# 1stschem.net
KiCad netlist of a schematic drawn in EAGLE
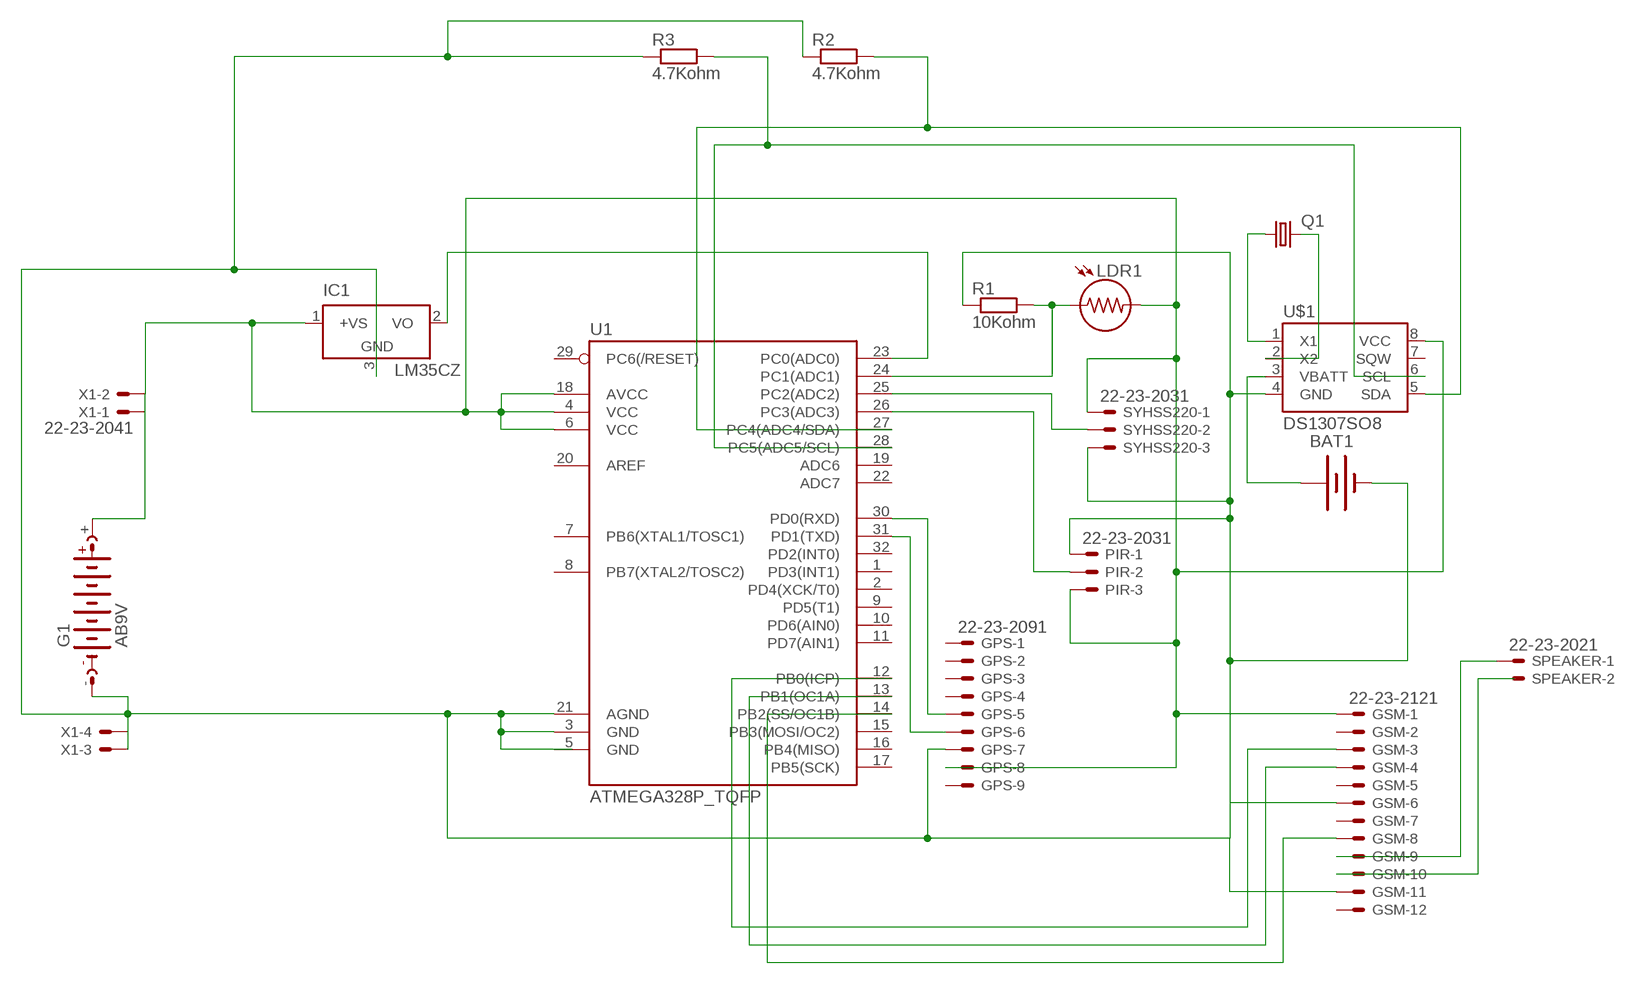
[diagram p0: schematic, sheet 1]

(export (version "E")
  (design (tool "Eeschema 10.0.6"))
  (components
    (comp (ref "BAT1")
      (value "BATTERY20PTH")
      (footprint "eagle-import:BATTCOM_20MM_PTH")
      (libsource (lib "eagle-import") (part "BATTERY20PTH"))
    )
    (comp (ref "G1")
      (value "AB9V")
      (footprint "eagle-import:AB9V")
      (libsource (lib "eagle-import") (part "AB9V"))
    )
    (comp (ref "GPS")
      (value "22-23-2091")
      (footprint "eagle-import:22-23-2091")
      (fields (field (name "MF") "MOLEX"))
      (libsource (lib "eagle-import") (part "22-23-2091"))
    )
    (comp (ref "GSM")
      (value "22-23-2121")
      (footprint "eagle-import:22-23-2121")
      (fields (field (name "MF") "MOLEX"))
      (libsource (lib "eagle-import") (part "22-23-2121"))
    )
    (comp (ref "IC1")
      (value "LM35CZ")
      (footprint "eagle-import:TO92")
      (libsource (lib "eagle-import") (part "LM35CZ"))
    )
    (comp (ref "LDR1")
      (value "LDR5MM")
      (footprint "eagle-import:LDR338-54C")
      (libsource (lib "eagle-import") (part "LDR5MM"))
    )
    (comp (ref "PIR")
      (value "22-23-2031")
      (footprint "eagle-import:22-23-2031")
      (fields (field (name "MF") "MOLEX"))
      (libsource (lib "eagle-import") (part "22-23-2031"))
    )
    (comp (ref "Q1")
      (value "CRYSTALTC26H")
      (footprint "eagle-import:TC26H")
      (libsource (lib "eagle-import") (part "CRYSTALTC26H"))
    )
    (comp (ref "R1")
      (value "10Kohm")
      (footprint "eagle-import:R0207_4")
      (libsource (lib "eagle-import") (part "6MM-EU4"))
    )
    (comp (ref "R2")
      (value "4.7Kohm")
      (footprint "eagle-import:R0207_4")
      (libsource (lib "eagle-import") (part "6MM-EU4"))
    )
    (comp (ref "R3")
      (value "4.7Kohm")
      (footprint "eagle-import:R0207_4")
      (libsource (lib "eagle-import") (part "6MM-EU4"))
    )
    (comp (ref "SPEAKER")
      (value "22-23-2021")
      (footprint "eagle-import:22-23-2021")
      (fields (field (name "MF") "MOLEX"))
      (libsource (lib "eagle-import") (part "22-23-2021"))
    )
    (comp (ref "SYHSS220")
      (value "22-23-2031")
      (footprint "eagle-import:22-23-2031")
      (fields (field (name "MF") "MOLEX"))
      (libsource (lib "eagle-import") (part "22-23-2031"))
    )
    (comp (ref "U$1")
      (value "DS1307SO8")
      (footprint "eagle-import:SO08")
      (libsource (lib "eagle-import") (part "DS1307SO8"))
    )
    (comp (ref "U1")
      (value "ATMEGA328P_TQFP")
      (footprint "eagle-import:TQFP32-08")
      (libsource (lib "eagle-import") (part "ATMEGA328P_TQFP"))
    )
    (comp (ref "X1")
      (value "22-23-2041")
      (footprint "eagle-import:22-23-2041")
      (fields (field (name "MF") "MOLEX"))
      (libsource (lib "eagle-import") (part "22-23-2041"))
    )
  )
  (nets
    (net (code "1") (name "Net-(BAT1-+)") (class "Default")
      (node (ref "BAT1") (pin "1") (pinfunction "+_1") (pintype "power_in"))
      (node (ref "U$1") (pin "3") (pinfunction "VBATT_3") (pintype "bidirectional"))
    )
    (net (code "2") (name "Net-(BAT1--)") (class "Default")
      (node (ref "BAT1") (pin "2") (pinfunction "-_2") (pintype "power_in"))
      (node (ref "G1") (pin "-") (pinfunction "-_-") (pintype "passive"))
      (node (ref "GPS") (pin "7") (pinfunction "S_7") (pintype "passive"))
      (node (ref "GSM") (pin "11") (pinfunction "S_11") (pintype "passive"))
      (node (ref "GSM") (pin "6") (pinfunction "S_6") (pintype "passive"))
      (node (ref "IC1") (pin "3") (pinfunction "GND_3") (pintype "power_in"))
      (node (ref "PIR") (pin "1") (pinfunction "S_1") (pintype "passive"))
      (node (ref "R1") (pin "1") (pinfunction "1_1") (pintype "passive"))
      (node (ref "R2") (pin "1") (pinfunction "1_1") (pintype "passive"))
      (node (ref "R3") (pin "1") (pinfunction "1_1") (pintype "passive"))
      (node (ref "SYHSS220") (pin "3") (pinfunction "S_3") (pintype "passive"))
      (node (ref "U$1") (pin "4") (pinfunction "GND_4") (pintype "bidirectional"))
      (node (ref "U1") (pin "21") (pinfunction "AGND_21") (pintype "bidirectional"))
      (node (ref "U1") (pin "3") (pinfunction "GND_3") (pintype "bidirectional"))
      (node (ref "X1") (pin "3") (pinfunction "S_3") (pintype "passive"))
      (node (ref "X1") (pin "4") (pinfunction "S_4") (pintype "passive"))
    )
    (net (code "3") (name "Net-(GPSE-S)") (class "Default")
      (node (ref "GPS") (pin "5") (pinfunction "S_5") (pintype "passive"))
      (node (ref "U1") (pin "30") (pinfunction "PD0(RXD)_30") (pintype "bidirectional"))
    )
    (net (code "4") (name "Net-(GPSF-S)") (class "Default")
      (node (ref "GPS") (pin "6") (pinfunction "S_6") (pintype "passive"))
      (node (ref "U1") (pin "31") (pinfunction "PD1(TXD)_31") (pintype "bidirectional"))
    )
    (net (code "5") (name "Net-(GPSH-S)") (class "Default")
      (node (ref "G1") (pin "+") (pinfunction "+_+") (pintype "passive"))
      (node (ref "GPS") (pin "8") (pinfunction "S_8") (pintype "passive"))
      (node (ref "GSM") (pin "1") (pinfunction "S_1") (pintype "passive"))
      (node (ref "IC1") (pin "1") (pinfunction "+VS_1") (pintype "input"))
      (node (ref "LDR1") (pin "2") (pinfunction "2_2") (pintype "passive"))
      (node (ref "PIR") (pin "3") (pinfunction "S_3") (pintype "passive"))
      (node (ref "SYHSS220") (pin "1") (pinfunction "S_1") (pintype "passive"))
      (node (ref "U$1") (pin "8") (pinfunction "VCC_8") (pintype "bidirectional"))
      (node (ref "U1") (pin "18") (pinfunction "AVCC_18") (pintype "bidirectional"))
      (node (ref "U1") (pin "4") (pinfunction "VCC_4") (pintype "bidirectional"))
      (node (ref "U1") (pin "6") (pinfunction "VCC_6") (pintype "bidirectional"))
      (node (ref "X1") (pin "1") (pinfunction "S_1") (pintype "passive"))
      (node (ref "X1") (pin "2") (pinfunction "S_2") (pintype "passive"))
    )
    (net (code "6") (name "Net-(GSMF-S)") (class "Default")
      (node (ref "GSM") (pin "3") (pinfunction "S_3") (pintype "passive"))
      (node (ref "U1") (pin "12") (pinfunction "PB0(ICP)_12") (pintype "bidirectional"))
    )
    (net (code "7") (name "Net-(GSMG-S)") (class "Default")
      (node (ref "GSM") (pin "4") (pinfunction "S_4") (pintype "passive"))
      (node (ref "U1") (pin "13") (pinfunction "PB1(OC1A)_13") (pintype "bidirectional"))
    )
    (net (code "8") (name "Net-(GSMK-S)") (class "Default")
      (node (ref "GSM") (pin "8") (pinfunction "S_8") (pintype "passive"))
      (node (ref "U1") (pin "14") (pinfunction "PB2(SS/OC1B)_14") (pintype "bidirectional"))
    )
    (net (code "9") (name "Net-(GSML-S)") (class "Default")
      (node (ref "GSM") (pin "9") (pinfunction "S_9") (pintype "passive"))
      (node (ref "SPEAKER") (pin "1") (pinfunction "S_1") (pintype "passive"))
    )
    (net (code "10") (name "Net-(IC1-VO)") (class "Default")
      (node (ref "IC1") (pin "2") (pinfunction "VO_2") (pintype "input"))
      (node (ref "U1") (pin "23") (pinfunction "PC0(ADC0)_23") (pintype "bidirectional"))
    )
    (net (code "11") (name "Net-(PIRB-S)") (class "Default")
      (node (ref "PIR") (pin "2") (pinfunction "S_2") (pintype "passive"))
      (node (ref "U1") (pin "26") (pinfunction "PC3(ADC3)_26") (pintype "bidirectional"))
    )
    (net (code "12") (name "Net-(SYHSS220B-S)") (class "Default")
      (node (ref "SYHSS220") (pin "2") (pinfunction "S_2") (pintype "passive"))
      (node (ref "U1") (pin "25") (pinfunction "PC2(ADC2)_25") (pintype "bidirectional"))
    )
    (net (code "13") (name "Net-(U$1-SCL)") (class "Default")
      (node (ref "R3") (pin "2") (pinfunction "2_2") (pintype "passive"))
      (node (ref "U$1") (pin "6") (pinfunction "SCL_6") (pintype "bidirectional"))
      (node (ref "U1") (pin "28") (pinfunction "PC5(ADC5/SCL)_28") (pintype "bidirectional"))
    )
    (net (code "14") (name "Net-(U$1-SDA)") (class "Default")
      (node (ref "R2") (pin "2") (pinfunction "2_2") (pintype "passive"))
      (node (ref "U$1") (pin "5") (pinfunction "SDA_5") (pintype "bidirectional"))
      (node (ref "U1") (pin "27") (pinfunction "PC4(ADC4/SDA)_27") (pintype "bidirectional"))
    )
    (net (code "15") (name "Net-(U$1-X1)") (class "Default")
      (node (ref "Q1") (pin "1") (pinfunction "1_1") (pintype "passive"))
      (node (ref "U$1") (pin "1") (pinfunction "X1_1") (pintype "bidirectional"))
    )
    (net (code "16") (name "Net-(U$1-X2)") (class "Default")
      (node (ref "Q1") (pin "2") (pinfunction "2_2") (pintype "passive"))
      (node (ref "U$1") (pin "2") (pinfunction "X2_2") (pintype "bidirectional"))
    )
    (net (code "17") (name "Net-(U1-PC1(ADC1))") (class "Default")
      (node (ref "LDR1") (pin "1") (pinfunction "1_1") (pintype "passive"))
      (node (ref "R1") (pin "2") (pinfunction "2_2") (pintype "passive"))
      (node (ref "U1") (pin "24") (pinfunction "PC1(ADC1)_24") (pintype "bidirectional"))
    )
    (net (code "18") (name "unconnected-(GPSA-S-Pad1)") (class "Default")
      (node (ref "GPS") (pin "1") (pinfunction "S_1") (pintype "passive"))
    )
    (net (code "19") (name "unconnected-(GPSB-S-Pad2)") (class "Default")
      (node (ref "GPS") (pin "2") (pinfunction "S_2") (pintype "passive"))
    )
    (net (code "20") (name "unconnected-(GPSC-S-Pad3)") (class "Default")
      (node (ref "GPS") (pin "3") (pinfunction "S_3") (pintype "passive"))
    )
    (net (code "21") (name "unconnected-(GPSD-S-Pad4)") (class "Default")
      (node (ref "GPS") (pin "4") (pinfunction "S_4") (pintype "passive"))
    )
    (net (code "22") (name "unconnected-(GPSI-S-Pad9)") (class "Default")
      (node (ref "GPS") (pin "9") (pinfunction "S_9") (pintype "passive"))
    )
    (net (code "23") (name "unconnected-(GSMB-S-Pad10)") (class "Default")
      (node (ref "GSM") (pin "10") (pinfunction "S_10") (pintype "passive"))
    )
    (net (code "24") (name "unconnected-(GSMD-S-Pad12)") (class "Default")
      (node (ref "GSM") (pin "12") (pinfunction "S_12") (pintype "passive"))
    )
    (net (code "25") (name "unconnected-(GSME-S-Pad2)") (class "Default")
      (node (ref "GSM") (pin "2") (pinfunction "S_2") (pintype "passive"))
    )
    (net (code "26") (name "unconnected-(GSMH-S-Pad5)") (class "Default")
      (node (ref "GSM") (pin "5") (pinfunction "S_5") (pintype "passive"))
    )
    (net (code "27") (name "unconnected-(GSMJ-S-Pad7)") (class "Default")
      (node (ref "GSM") (pin "7") (pinfunction "S_7") (pintype "passive"))
    )
    (net (code "28") (name "unconnected-(SPEAKERB-S-Pad2)") (class "Default")
      (node (ref "SPEAKER") (pin "2") (pinfunction "S_2") (pintype "passive"))
    )
    (net (code "29") (name "unconnected-(U$1-SQW-Pad7)") (class "Default")
      (node (ref "U$1") (pin "7") (pinfunction "SQW_7") (pintype "bidirectional"))
    )
    (net (code "30") (name "unconnected-(U1-ADC6-Pad19)") (class "Default")
      (node (ref "U1") (pin "19") (pinfunction "ADC6_19") (pintype "bidirectional"))
    )
    (net (code "31") (name "unconnected-(U1-ADC7-Pad22)") (class "Default")
      (node (ref "U1") (pin "22") (pinfunction "ADC7_22") (pintype "bidirectional"))
    )
    (net (code "32") (name "unconnected-(U1-AREF-Pad20)") (class "Default")
      (node (ref "U1") (pin "20") (pinfunction "AREF_20") (pintype "bidirectional"))
    )
    (net (code "33") (name "unconnected-(U1-GND-Pad5)") (class "Default")
      (node (ref "U1") (pin "5") (pinfunction "GND_5") (pintype "bidirectional"))
    )
    (net (code "34") (name "unconnected-(U1-PB3(MOSI{slash}OC2)-Pad15)") (class "Default")
      (node (ref "U1") (pin "15") (pinfunction "PB3(MOSI/OC2)_15") (pintype "bidirectional"))
    )
    (net (code "35") (name "unconnected-(U1-PB4(MISO)-Pad16)") (class "Default")
      (node (ref "U1") (pin "16") (pinfunction "PB4(MISO)_16") (pintype "bidirectional"))
    )
    (net (code "36") (name "unconnected-(U1-PB5(SCK)-Pad17)") (class "Default")
      (node (ref "U1") (pin "17") (pinfunction "PB5(SCK)_17") (pintype "bidirectional"))
    )
    (net (code "37") (name "unconnected-(U1-PB6(XTAL1{slash}TOSC1)-Pad7)") (class "Default")
      (node (ref "U1") (pin "7") (pinfunction "PB6(XTAL1/TOSC1)_7") (pintype "bidirectional"))
    )
    (net (code "38") (name "unconnected-(U1-PB7(XTAL2{slash}TOSC2)-Pad8)") (class "Default")
      (node (ref "U1") (pin "8") (pinfunction "PB7(XTAL2/TOSC2)_8") (pintype "bidirectional"))
    )
    (net (code "39") (name "unconnected-(U1-PC6({slash}RESET)-Pad29)") (class "Default")
      (node (ref "U1") (pin "29") (pinfunction "PC6(/RESET)_29") (pintype "bidirectional"))
    )
    (net (code "40") (name "unconnected-(U1-PD2(INT0)-Pad32)") (class "Default")
      (node (ref "U1") (pin "32") (pinfunction "PD2(INT0)_32") (pintype "bidirectional"))
    )
    (net (code "41") (name "unconnected-(U1-PD3(INT1)-Pad1)") (class "Default")
      (node (ref "U1") (pin "1") (pinfunction "PD3(INT1)_1") (pintype "bidirectional"))
    )
    (net (code "42") (name "unconnected-(U1-PD4(XCK{slash}T0)-Pad2)") (class "Default")
      (node (ref "U1") (pin "2") (pinfunction "PD4(XCK/T0)_2") (pintype "bidirectional"))
    )
    (net (code "43") (name "unconnected-(U1-PD5(T1)-Pad9)") (class "Default")
      (node (ref "U1") (pin "9") (pinfunction "PD5(T1)_9") (pintype "bidirectional"))
    )
    (net (code "44") (name "unconnected-(U1-PD6(AIN0)-Pad10)") (class "Default")
      (node (ref "U1") (pin "10") (pinfunction "PD6(AIN0)_10") (pintype "bidirectional"))
    )
    (net (code "45") (name "unconnected-(U1-PD7(AIN1)-Pad11)") (class "Default")
      (node (ref "U1") (pin "11") (pinfunction "PD7(AIN1)_11") (pintype "bidirectional"))
    )
  )
)
